# altimeter.net
KiCad netlist of a schematic drawn in EAGLE
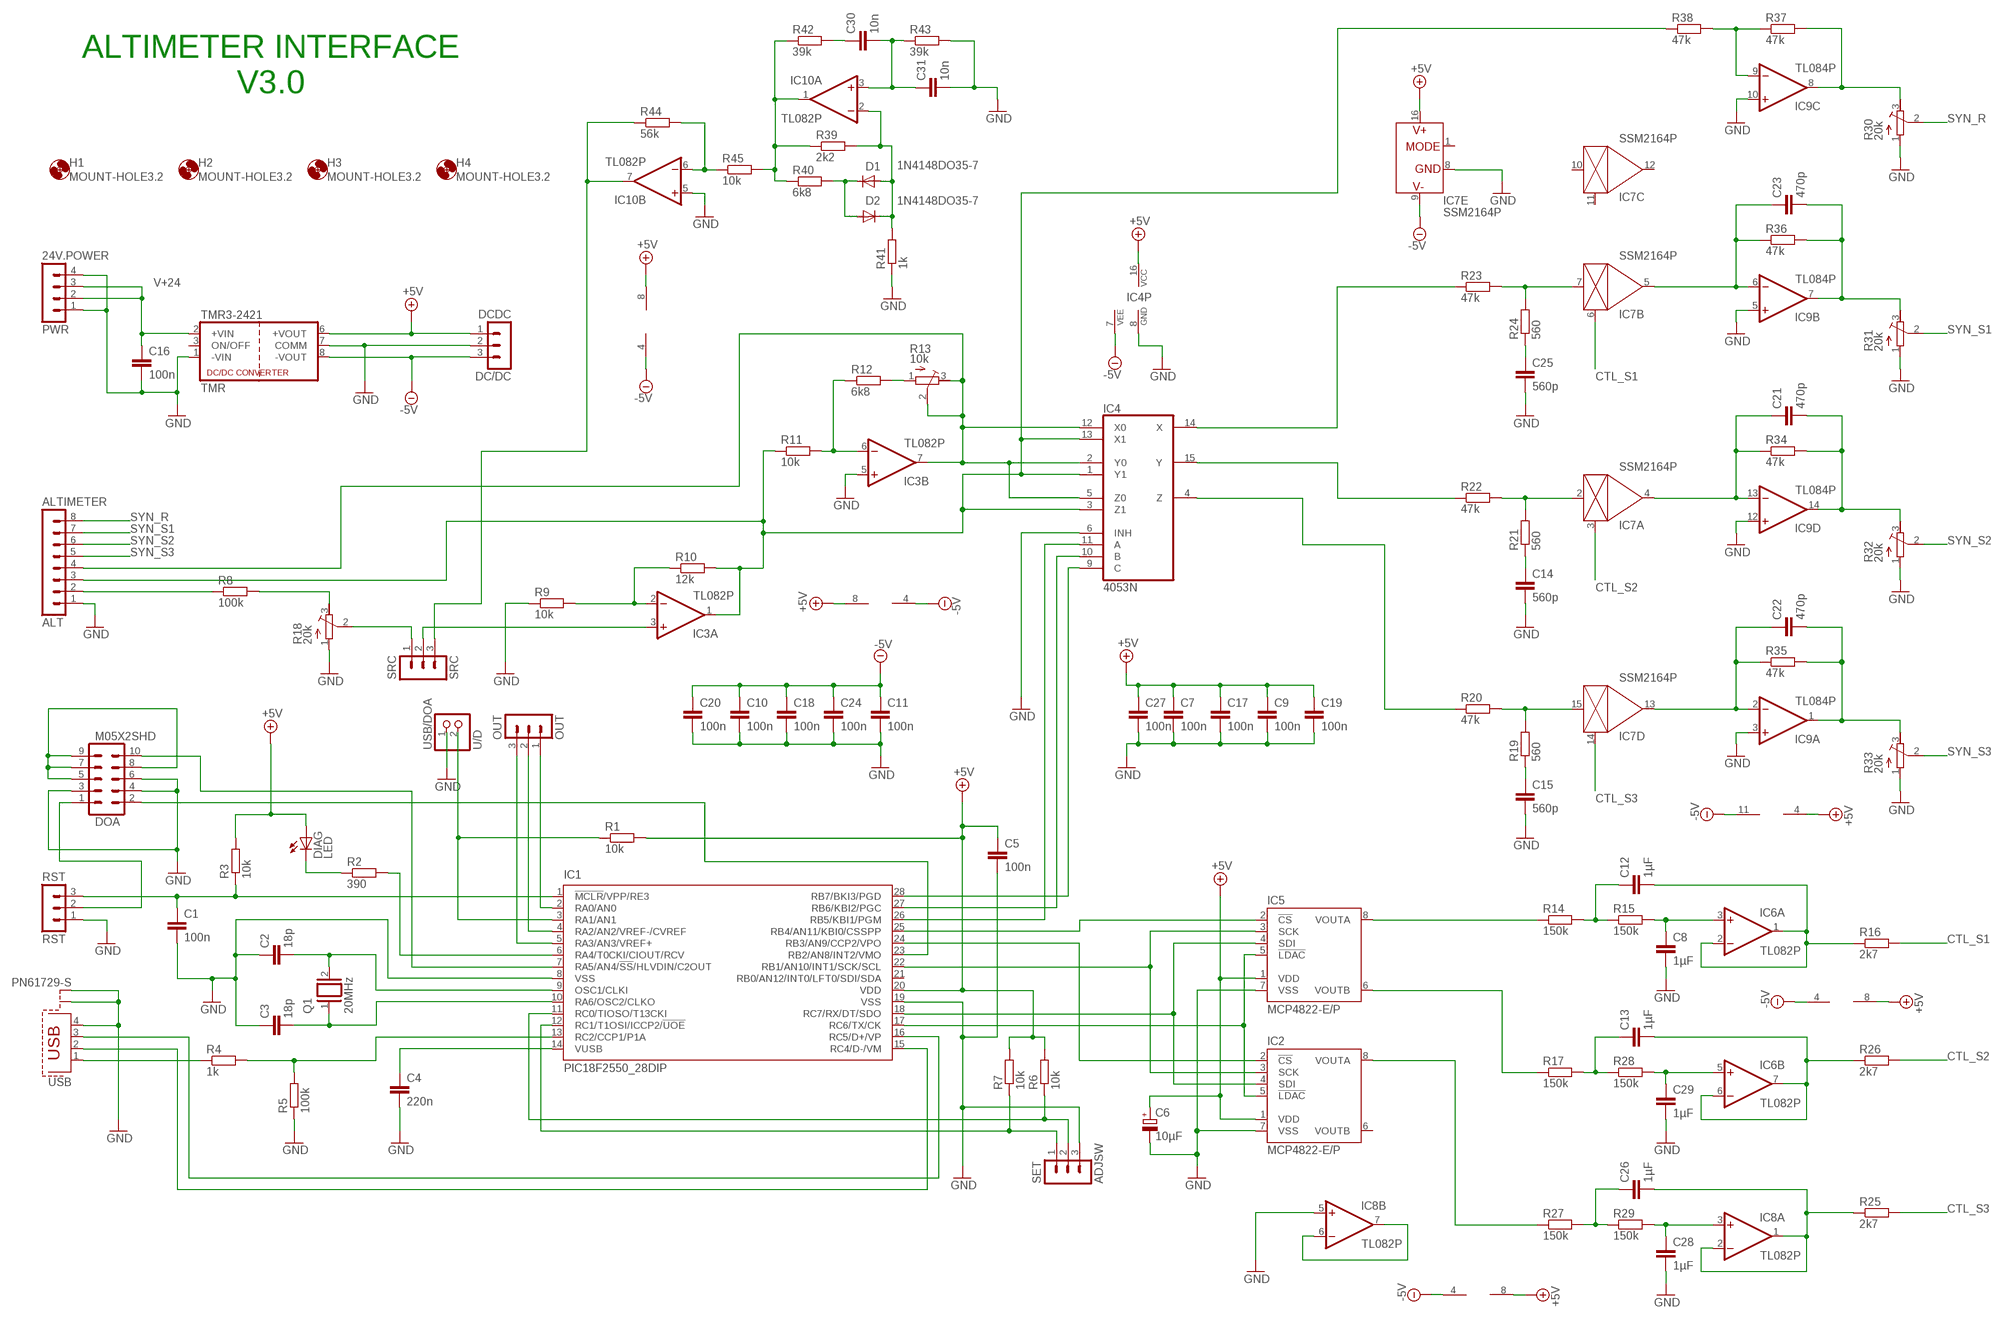
[diagram p0: schematic, sheet 1]

(export (version "E")
  (design (tool "Eeschema 10.0.6"))
  (components
    (comp (ref "24V.POWER")
      (value "PWR")
      (footprint "eagle-import:MA04-1")
      (libsource (lib "eagle-import") (part "MA04-1"))
    )
    (comp (ref "ADJSW")
      (value "SET")
      (footprint "eagle-import:MA03-1")
      (libsource (lib "eagle-import") (part "MA03-1"))
    )
    (comp (ref "ALTIMETER")
      (value "ALT")
      (footprint "eagle-import:MA08-1")
      (libsource (lib "eagle-import") (part "MA08-1"))
    )
    (comp (ref "C1")
      (value "100n")
      (footprint "eagle-import:C025-025X050")
      (libsource (lib "eagle-import") (part "C-EU025-025X050"))
    )
    (comp (ref "C2")
      (value "18p")
      (footprint "eagle-import:C025-025X050")
      (libsource (lib "eagle-import") (part "C-EU025-025X050"))
    )
    (comp (ref "C3")
      (value "18p")
      (footprint "eagle-import:C025-025X050")
      (libsource (lib "eagle-import") (part "C-EU025-025X050"))
    )
    (comp (ref "C4")
      (value "220n")
      (footprint "eagle-import:C5B3")
      (libsource (lib "eagle-import") (part "C5/3"))
    )
    (comp (ref "C5")
      (value "100n")
      (footprint "eagle-import:C025-025X050")
      (libsource (lib "eagle-import") (part "C-EU025-025X050"))
    )
    (comp (ref "C6")
      (value "10µF")
      (footprint "eagle-import:E2,5-5")
      (libsource (lib "eagle-import") (part "CPOL-EUE2.5-5"))
    )
    (comp (ref "C7")
      (value "100n")
      (footprint "eagle-import:C025-025X050")
      (libsource (lib "eagle-import") (part "C-EU025-025X050"))
    )
    (comp (ref "C8")
      (value "1µF")
      (footprint "eagle-import:C025-025X050")
      (libsource (lib "eagle-import") (part "C-EU025-025X050"))
    )
    (comp (ref "C9")
      (value "100n")
      (footprint "eagle-import:C025-025X050")
      (libsource (lib "eagle-import") (part "C-EU025-025X050"))
    )
    (comp (ref "C10")
      (value "100n")
      (footprint "eagle-import:C025-025X050")
      (libsource (lib "eagle-import") (part "C-EU025-025X050"))
    )
    (comp (ref "C11")
      (value "100n")
      (footprint "eagle-import:C025-025X050")
      (libsource (lib "eagle-import") (part "C-EU025-025X050"))
    )
    (comp (ref "C12")
      (value "1µF")
      (footprint "eagle-import:C025-025X050")
      (libsource (lib "eagle-import") (part "C-EU025-025X050"))
    )
    (comp (ref "C13")
      (value "1µF")
      (footprint "eagle-import:C025-025X050")
      (libsource (lib "eagle-import") (part "C-EU025-025X050"))
    )
    (comp (ref "C14")
      (value "560p")
      (footprint "eagle-import:C025-025X050")
      (libsource (lib "eagle-import") (part "C-EU025-025X050"))
    )
    (comp (ref "C15")
      (value "560p")
      (footprint "eagle-import:C025-025X050")
      (libsource (lib "eagle-import") (part "C-EU025-025X050"))
    )
    (comp (ref "C16")
      (value "100n")
      (footprint "eagle-import:C025-025X050")
      (libsource (lib "eagle-import") (part "C-EU025-025X050"))
    )
    (comp (ref "C17")
      (value "100n")
      (footprint "eagle-import:C025-025X050")
      (libsource (lib "eagle-import") (part "C-EU025-025X050"))
    )
    (comp (ref "C18")
      (value "100n")
      (footprint "eagle-import:C025-025X050")
      (libsource (lib "eagle-import") (part "C-EU025-025X050"))
    )
    (comp (ref "C19")
      (value "100n")
      (footprint "eagle-import:C025-025X050")
      (libsource (lib "eagle-import") (part "C-EU025-025X050"))
    )
    (comp (ref "C20")
      (value "100n")
      (footprint "eagle-import:C025-025X050")
      (libsource (lib "eagle-import") (part "C-EU025-025X050"))
    )
    (comp (ref "C21")
      (value "470p")
      (footprint "eagle-import:C025-025X050")
      (libsource (lib "eagle-import") (part "C-EU025-025X050"))
    )
    (comp (ref "C22")
      (value "470p")
      (footprint "eagle-import:C025-025X050")
      (libsource (lib "eagle-import") (part "C-EU025-025X050"))
    )
    (comp (ref "C23")
      (value "470p")
      (footprint "eagle-import:C025-025X050")
      (libsource (lib "eagle-import") (part "C-EU025-025X050"))
    )
    (comp (ref "C24")
      (value "100n")
      (footprint "eagle-import:C025-025X050")
      (libsource (lib "eagle-import") (part "C-EU025-025X050"))
    )
    (comp (ref "C25")
      (value "560p")
      (footprint "eagle-import:C025-025X050")
      (libsource (lib "eagle-import") (part "C-EU025-025X050"))
    )
    (comp (ref "C26")
      (value "1µF")
      (footprint "eagle-import:C025-025X050")
      (libsource (lib "eagle-import") (part "C-EU025-025X050"))
    )
    (comp (ref "C27")
      (value "100n")
      (footprint "eagle-import:C025-025X050")
      (libsource (lib "eagle-import") (part "C-EU025-025X050"))
    )
    (comp (ref "C28")
      (value "1µF")
      (footprint "eagle-import:C025-025X050")
      (libsource (lib "eagle-import") (part "C-EU025-025X050"))
    )
    (comp (ref "C29")
      (value "1µF")
      (footprint "eagle-import:C025-025X050")
      (libsource (lib "eagle-import") (part "C-EU025-025X050"))
    )
    (comp (ref "C30")
      (value "10n")
      (footprint "eagle-import:C025-025X050")
      (libsource (lib "eagle-import") (part "C-EU025-025X050"))
    )
    (comp (ref "C31")
      (value "10n")
      (footprint "eagle-import:C025-025X050")
      (libsource (lib "eagle-import") (part "C-EU025-025X050"))
    )
    (comp (ref "D1")
      (value "1N4148DO35-7")
      (footprint "eagle-import:DO35-7")
      (libsource (lib "eagle-import") (part "1N4148DO35-7"))
    )
    (comp (ref "D2")
      (value "1N4148DO35-7")
      (footprint "eagle-import:DO35-7")
      (libsource (lib "eagle-import") (part "1N4148DO35-7"))
    )
    (comp (ref "DC/DC")
      (value "DCDC")
      (footprint "eagle-import:MA03-1")
      (libsource (lib "eagle-import") (part "MA03-1"))
    )
    (comp (ref "DIAG")
      (value "LED")
      (footprint "eagle-import:LED3MM")
      (libsource (lib "eagle-import") (part "LED3MM"))
    )
    (comp (ref "DOA")
      (value "M05X2SHD")
      (footprint "eagle-import:2X5-SHROUDED")
      (libsource (lib "eagle-import") (part "M05X2SHD"))
    )
    (comp (ref "H1")
      (value "MOUNT-HOLE3.2")
      (footprint "eagle-import:3,2")
      (libsource (lib "eagle-import") (part "MOUNT-HOLE3.2"))
    )
    (comp (ref "H2")
      (value "MOUNT-HOLE3.2")
      (footprint "eagle-import:3,2")
      (libsource (lib "eagle-import") (part "MOUNT-HOLE3.2"))
    )
    (comp (ref "H3")
      (value "MOUNT-HOLE3.2")
      (footprint "eagle-import:3,2")
      (libsource (lib "eagle-import") (part "MOUNT-HOLE3.2"))
    )
    (comp (ref "H4")
      (value "MOUNT-HOLE3.2")
      (footprint "eagle-import:3,2")
      (libsource (lib "eagle-import") (part "MOUNT-HOLE3.2"))
    )
    (comp (ref "IC1")
      (value "PIC18F2550_28DIP")
      (footprint "eagle-import:DIL28-3")
      (fields (field (name "MF") "MICROCHIP") (field (name "MPN") "PIC18F2550-I/SP"))
      (libsource (lib "eagle-import") (part "PIC18F2_28DIP550"))
    )
    (comp (ref "IC2")
      (value "MCP4822-E/P")
      (footprint "eagle-import:DIL08")
      (libsource (lib "eagle-import") (part "MCP4822-E/P"))
    )
    (comp (ref "IC3")
      (value "TL082P")
      (footprint "eagle-import:DIL08")
      (libsource (lib "eagle-import") (part "TL082P"))
    )
    (comp (ref "IC4")
      (value "4053N")
      (footprint "eagle-import:DIL16")
      (libsource (lib "eagle-import") (part "4053N"))
    )
    (comp (ref "IC5")
      (value "MCP4822-E/P")
      (footprint "eagle-import:DIL08")
      (libsource (lib "eagle-import") (part "MCP4822-E/P"))
    )
    (comp (ref "IC6")
      (value "TL082P")
      (footprint "eagle-import:DIL08")
      (libsource (lib "eagle-import") (part "TL082P"))
    )
    (comp (ref "IC7")
      (value "SSM2164P")
      (footprint "eagle-import:DIL16")
      (libsource (lib "eagle-import") (part "SSM2164P"))
    )
    (comp (ref "IC8")
      (value "TL082P")
      (footprint "eagle-import:DIL08")
      (libsource (lib "eagle-import") (part "TL082P"))
    )
    (comp (ref "IC9")
      (value "TL084P")
      (footprint "eagle-import:DIL14")
      (libsource (lib "eagle-import") (part "TL084P"))
    )
    (comp (ref "IC10")
      (value "TL082P")
      (footprint "eagle-import:DIL08")
      (libsource (lib "eagle-import") (part "TL082P"))
    )
    (comp (ref "OUT")
      (value "OUT")
      (footprint "eagle-import:MA03-1")
      (libsource (lib "eagle-import") (part "MA03-1"))
    )
    (comp (ref "Q1")
      (value "20MHz")
      (footprint "eagle-import:QS")
      (libsource (lib "eagle-import") (part "XTAL/S"))
    )
    (comp (ref "R1")
      (value "10k")
      (footprint "eagle-import:0204_7")
      (libsource (lib "eagle-import") (part "R-EU_0204/7"))
    )
    (comp (ref "R2")
      (value "390")
      (footprint "eagle-import:0204_7")
      (libsource (lib "eagle-import") (part "R-EU_0204/7"))
    )
    (comp (ref "R3")
      (value "10k")
      (footprint "eagle-import:0204_7")
      (libsource (lib "eagle-import") (part "R-EU_0204/7"))
    )
    (comp (ref "R4")
      (value "1k")
      (footprint "eagle-import:0204_7")
      (libsource (lib "eagle-import") (part "R-EU_0204/7"))
    )
    (comp (ref "R5")
      (value "100k")
      (footprint "eagle-import:0204_7")
      (libsource (lib "eagle-import") (part "R-EU_0204/7"))
    )
    (comp (ref "R6")
      (value "10k")
      (footprint "eagle-import:0204_7")
      (libsource (lib "eagle-import") (part "R-EU_0204/7"))
    )
    (comp (ref "R7")
      (value "10k")
      (footprint "eagle-import:0204_7")
      (libsource (lib "eagle-import") (part "R-EU_0204/7"))
    )
    (comp (ref "R8")
      (value "100k")
      (footprint "eagle-import:0204_7")
      (libsource (lib "eagle-import") (part "R-EU_0204/7"))
    )
    (comp (ref "R9")
      (value "10k")
      (footprint "eagle-import:0204_7")
      (libsource (lib "eagle-import") (part "R-EU_0204/7"))
    )
    (comp (ref "R10")
      (value "12k")
      (footprint "eagle-import:0204_7")
      (libsource (lib "eagle-import") (part "R-EU_0204/7"))
    )
    (comp (ref "R11")
      (value "10k")
      (footprint "eagle-import:0204_7")
      (libsource (lib "eagle-import") (part "R-EU_0204/7"))
    )
    (comp (ref "R12")
      (value "6k8")
      (footprint "eagle-import:0204_7")
      (libsource (lib "eagle-import") (part "R-EU_0204/7"))
    )
    (comp (ref "R13")
      (value "10k")
      (footprint "eagle-import:RTRIM64Z")
      (libsource (lib "eagle-import") (part "R-TRIMM64Z"))
    )
    (comp (ref "R14")
      (value "150k")
      (footprint "eagle-import:0204_7")
      (libsource (lib "eagle-import") (part "R-EU_0204/7"))
    )
    (comp (ref "R15")
      (value "150k")
      (footprint "eagle-import:0204_7")
      (libsource (lib "eagle-import") (part "R-EU_0204/7"))
    )
    (comp (ref "R16")
      (value "2k7")
      (footprint "eagle-import:0204_7")
      (libsource (lib "eagle-import") (part "R-EU_0204/7"))
    )
    (comp (ref "R17")
      (value "150k")
      (footprint "eagle-import:0204_7")
      (libsource (lib "eagle-import") (part "R-EU_0204/7"))
    )
    (comp (ref "R18")
      (value "20k")
      (footprint "eagle-import:RTRIM64Z")
      (libsource (lib "eagle-import") (part "R-TRIMM64Z"))
    )
    (comp (ref "R19")
      (value "560")
      (footprint "eagle-import:0204_7")
      (libsource (lib "eagle-import") (part "R-EU_0204/7"))
    )
    (comp (ref "R20")
      (value "47k")
      (footprint "eagle-import:0204_7")
      (libsource (lib "eagle-import") (part "R-EU_0204/7"))
    )
    (comp (ref "R21")
      (value "560")
      (footprint "eagle-import:0204_7")
      (libsource (lib "eagle-import") (part "R-EU_0204/7"))
    )
    (comp (ref "R22")
      (value "47k")
      (footprint "eagle-import:0204_7")
      (libsource (lib "eagle-import") (part "R-EU_0204/7"))
    )
    (comp (ref "R23")
      (value "47k")
      (footprint "eagle-import:0204_7")
      (libsource (lib "eagle-import") (part "R-EU_0204/7"))
    )
    (comp (ref "R24")
      (value "560")
      (footprint "eagle-import:0204_7")
      (libsource (lib "eagle-import") (part "R-EU_0204/7"))
    )
    (comp (ref "R25")
      (value "2k7")
      (footprint "eagle-import:0204_7")
      (libsource (lib "eagle-import") (part "R-EU_0204/7"))
    )
    (comp (ref "R26")
      (value "2k7")
      (footprint "eagle-import:0204_7")
      (libsource (lib "eagle-import") (part "R-EU_0204/7"))
    )
    (comp (ref "R27")
      (value "150k")
      (footprint "eagle-import:0204_7")
      (libsource (lib "eagle-import") (part "R-EU_0204/7"))
    )
    (comp (ref "R28")
      (value "150k")
      (footprint "eagle-import:0204_7")
      (libsource (lib "eagle-import") (part "R-EU_0204/7"))
    )
    (comp (ref "R29")
      (value "150k")
      (footprint "eagle-import:0204_7")
      (libsource (lib "eagle-import") (part "R-EU_0204/7"))
    )
    (comp (ref "R30")
      (value "20k")
      (footprint "eagle-import:RTRIM64Z")
      (libsource (lib "eagle-import") (part "R-TRIMM64Z"))
    )
    (comp (ref "R31")
      (value "20k")
      (footprint "eagle-import:RTRIM64Z")
      (libsource (lib "eagle-import") (part "R-TRIMM64Z"))
    )
    (comp (ref "R32")
      (value "20k")
      (footprint "eagle-import:RTRIM64Z")
      (libsource (lib "eagle-import") (part "R-TRIMM64Z"))
    )
    (comp (ref "R33")
      (value "20k")
      (footprint "eagle-import:RTRIM64Z")
      (libsource (lib "eagle-import") (part "R-TRIMM64Z"))
    )
    (comp (ref "R34")
      (value "47k")
      (footprint "eagle-import:0204_7")
      (libsource (lib "eagle-import") (part "R-EU_0204/7"))
    )
    (comp (ref "R35")
      (value "47k")
      (footprint "eagle-import:0204_7")
      (libsource (lib "eagle-import") (part "R-EU_0204/7"))
    )
    (comp (ref "R36")
      (value "47k")
      (footprint "eagle-import:0204_7")
      (libsource (lib "eagle-import") (part "R-EU_0204/7"))
    )
    (comp (ref "R37")
      (value "47k")
      (footprint "eagle-import:0204_7")
      (libsource (lib "eagle-import") (part "R-EU_0204/7"))
    )
    (comp (ref "R38")
      (value "47k")
      (footprint "eagle-import:0204_7")
      (libsource (lib "eagle-import") (part "R-EU_0204/7"))
    )
    (comp (ref "R39")
      (value "2k2")
      (footprint "eagle-import:0204_7")
      (libsource (lib "eagle-import") (part "R-EU_0204/7"))
    )
    (comp (ref "R40")
      (value "6k8")
      (footprint "eagle-import:0204_7")
      (libsource (lib "eagle-import") (part "R-EU_0204/7"))
    )
    (comp (ref "R41")
      (value "1k")
      (footprint "eagle-import:0204_7")
      (libsource (lib "eagle-import") (part "R-EU_0204/7"))
    )
    (comp (ref "R42")
      (value "39k")
      (footprint "eagle-import:0204_7")
      (libsource (lib "eagle-import") (part "R-EU_0204/7"))
    )
    (comp (ref "R43")
      (value "39k")
      (footprint "eagle-import:0204_7")
      (libsource (lib "eagle-import") (part "R-EU_0204/7"))
    )
    (comp (ref "R44")
      (value "56k")
      (footprint "eagle-import:0204_7")
      (libsource (lib "eagle-import") (part "R-EU_0204/7"))
    )
    (comp (ref "R45")
      (value "10k")
      (footprint "eagle-import:0204_7")
      (libsource (lib "eagle-import") (part "R-EU_0204/7"))
    )
    (comp (ref "RST")
      (value "RST")
      (footprint "eagle-import:MA03-1")
      (libsource (lib "eagle-import") (part "MA03-1"))
    )
    (comp (ref "SRC")
      (value "SRC")
      (footprint "eagle-import:MA03-1")
      (libsource (lib "eagle-import") (part "MA03-1"))
    )
    (comp (ref "TMR3-2421")
      (value "TMR")
      (footprint "eagle-import:TRACO_SIP-8")
      (libsource (lib "eagle-import") (part "TMR"))
    )
    (comp (ref "USB")
      (value "PN61729-S")
      (footprint "eagle-import:PN61729-S")
      (libsource (lib "eagle-import") (part "PN61729-S"))
    )
    (comp (ref "USB/DOA")
      (value "U/D")
      (footprint "eagle-import:1X02")
      (libsource (lib "eagle-import") (part "PINHD-1X2"))
    )
  )
  (nets
    (net (code "1") (name "+5V") (class "Default")
      (node (ref "C17") (pin "1") (pinfunction "1_1") (pintype "passive"))
      (node (ref "C19") (pin "1") (pinfunction "1_1") (pintype "passive"))
      (node (ref "C27") (pin "1") (pinfunction "1_1") (pintype "passive"))
      (node (ref "C5") (pin "1") (pinfunction "1_1") (pintype "passive"))
      (node (ref "C6") (pin "+") (pinfunction "+_+") (pintype "passive"))
      (node (ref "C7") (pin "1") (pinfunction "1_1") (pintype "passive"))
      (node (ref "C9") (pin "1") (pinfunction "1_1") (pintype "passive"))
      (node (ref "DC/DC") (pin "1") (pinfunction "1_1") (pintype "passive"))
      (node (ref "DIAG") (pin "A") (pinfunction "A_A") (pintype "passive"))
      (node (ref "IC1") (pin "20") (pinfunction "VDD_20") (pintype "power_in"))
      (node (ref "IC10") (pin "8") (pinfunction "V+_8") (pintype "power_in"))
      (node (ref "IC2") (pin "1") (pinfunction "VDD_1") (pintype "power_in"))
      (node (ref "IC3") (pin "8") (pinfunction "V+_8") (pintype "power_in"))
      (node (ref "IC4") (pin "16") (pinfunction "VCC_16") (pintype "power_in"))
      (node (ref "IC5") (pin "1") (pinfunction "VDD_1") (pintype "power_in"))
      (node (ref "IC6") (pin "8") (pinfunction "V+_8") (pintype "power_in"))
      (node (ref "IC7") (pin "16") (pinfunction "V+_16") (pintype "power_in"))
      (node (ref "IC8") (pin "8") (pinfunction "V+_8") (pintype "power_in"))
      (node (ref "IC9") (pin "4") (pinfunction "V+_4") (pintype "power_in"))
      (node (ref "R1") (pin "2") (pinfunction "2_2") (pintype "passive"))
      (node (ref "R3") (pin "2") (pinfunction "2_2") (pintype "passive"))
      (node (ref "R6") (pin "2") (pinfunction "2_2") (pintype "passive"))
      (node (ref "R7") (pin "2") (pinfunction "2_2") (pintype "passive"))
      (node (ref "TMR3-2421") (pin "6") (pinfunction "+VOUT_6") (pintype "passive"))
    )
    (net (code "2") (name "-5V") (class "Default")
      (node (ref "C10") (pin "1") (pinfunction "1_1") (pintype "passive"))
      (node (ref "C11") (pin "1") (pinfunction "1_1") (pintype "passive"))
      (node (ref "C18") (pin "1") (pinfunction "1_1") (pintype "passive"))
      (node (ref "C20") (pin "1") (pinfunction "1_1") (pintype "passive"))
      (node (ref "C24") (pin "1") (pinfunction "1_1") (pintype "passive"))
      (node (ref "DC/DC") (pin "3") (pinfunction "3_3") (pintype "passive"))
      (node (ref "IC10") (pin "4") (pinfunction "V-_4") (pintype "power_in"))
      (node (ref "IC3") (pin "4") (pinfunction "V-_4") (pintype "power_in"))
      (node (ref "IC4") (pin "7") (pinfunction "VEE_7") (pintype "power_in"))
      (node (ref "IC6") (pin "4") (pinfunction "V-_4") (pintype "power_in"))
      (node (ref "IC7") (pin "9") (pinfunction "V-_9") (pintype "power_in"))
      (node (ref "IC8") (pin "4") (pinfunction "V-_4") (pintype "power_in"))
      (node (ref "IC9") (pin "11") (pinfunction "V-_11") (pintype "power_in"))
      (node (ref "TMR3-2421") (pin "8") (pinfunction "-VOUT_8") (pintype "passive"))
    )
    (net (code "3") (name "/CTL_S1") (class "Default")
      (node (ref "IC7") (pin "6") (pinfunction "CTRL_6") (pintype "input"))
      (node (ref "R16") (pin "2") (pinfunction "2_2") (pintype "passive"))
    )
    (net (code "4") (name "/CTL_S2") (class "Default")
      (node (ref "IC7") (pin "3") (pinfunction "CTRL_3") (pintype "input"))
      (node (ref "R26") (pin "2") (pinfunction "2_2") (pintype "passive"))
    )
    (net (code "5") (name "/CTL_S3") (class "Default")
      (node (ref "IC7") (pin "14") (pinfunction "CTRL_14") (pintype "input"))
      (node (ref "R25") (pin "2") (pinfunction "2_2") (pintype "passive"))
    )
    (net (code "6") (name "/SYN_R") (class "Default")
      (node (ref "ALTIMETER") (pin "8") (pinfunction "8_8") (pintype "passive"))
      (node (ref "R30") (pin "2") (pinfunction "S_2") (pintype "passive"))
    )
    (net (code "7") (name "/SYN_S1") (class "Default")
      (node (ref "ALTIMETER") (pin "7") (pinfunction "7_7") (pintype "passive"))
      (node (ref "R31") (pin "2") (pinfunction "S_2") (pintype "passive"))
    )
    (net (code "8") (name "/SYN_S2") (class "Default")
      (node (ref "ALTIMETER") (pin "6") (pinfunction "6_6") (pintype "passive"))
      (node (ref "R32") (pin "2") (pinfunction "S_2") (pintype "passive"))
    )
    (net (code "9") (name "/SYN_S3") (class "Default")
      (node (ref "ALTIMETER") (pin "5") (pinfunction "5_5") (pintype "passive"))
      (node (ref "R33") (pin "2") (pinfunction "S_2") (pintype "passive"))
    )
    (net (code "10") (name "/V+24") (class "Default")
      (node (ref "24V.POWER") (pin "2") (pinfunction "2_2") (pintype "passive"))
      (node (ref "24V.POWER") (pin "3") (pinfunction "3_3") (pintype "passive"))
      (node (ref "C16") (pin "1") (pinfunction "1_1") (pintype "passive"))
      (node (ref "TMR3-2421") (pin "2") (pinfunction "+VIN_2") (pintype "passive"))
    )
    (net (code "11") (name "GND") (class "Default")
      (node (ref "24V.POWER") (pin "1") (pinfunction "1_1") (pintype "passive"))
      (node (ref "24V.POWER") (pin "4") (pinfunction "4_4") (pintype "passive"))
      (node (ref "ADJSW") (pin "3") (pinfunction "3_3") (pintype "passive"))
      (node (ref "ALTIMETER") (pin "1") (pinfunction "1_1") (pintype "passive"))
      (node (ref "C1") (pin "2") (pinfunction "2_2") (pintype "passive"))
      (node (ref "C10") (pin "2") (pinfunction "2_2") (pintype "passive"))
      (node (ref "C11") (pin "2") (pinfunction "2_2") (pintype "passive"))
      (node (ref "C14") (pin "2") (pinfunction "2_2") (pintype "passive"))
      (node (ref "C15") (pin "2") (pinfunction "2_2") (pintype "passive"))
      (node (ref "C16") (pin "2") (pinfunction "2_2") (pintype "passive"))
      (node (ref "C17") (pin "2") (pinfunction "2_2") (pintype "passive"))
      (node (ref "C18") (pin "2") (pinfunction "2_2") (pintype "passive"))
      (node (ref "C19") (pin "2") (pinfunction "2_2") (pintype "passive"))
      (node (ref "C2") (pin "1") (pinfunction "1_1") (pintype "passive"))
      (node (ref "C20") (pin "2") (pinfunction "2_2") (pintype "passive"))
      (node (ref "C24") (pin "2") (pinfunction "2_2") (pintype "passive"))
      (node (ref "C25") (pin "2") (pinfunction "2_2") (pintype "passive"))
      (node (ref "C27") (pin "2") (pinfunction "2_2") (pintype "passive"))
      (node (ref "C28") (pin "2") (pinfunction "2_2") (pintype "passive"))
      (node (ref "C29") (pin "2") (pinfunction "2_2") (pintype "passive"))
      (node (ref "C3") (pin "1") (pinfunction "1_1") (pintype "passive"))
      (node (ref "C31") (pin "2") (pinfunction "2_2") (pintype "passive"))
      (node (ref "C4") (pin "2") (pinfunction "2_2") (pintype "passive"))
      (node (ref "C5") (pin "2") (pinfunction "2_2") (pintype "passive"))
      (node (ref "C6") (pin "-") (pinfunction "-_-") (pintype "passive"))
      (node (ref "C7") (pin "2") (pinfunction "2_2") (pintype "passive"))
      (node (ref "C8") (pin "2") (pinfunction "2_2") (pintype "passive"))
      (node (ref "C9") (pin "2") (pinfunction "2_2") (pintype "passive"))
      (node (ref "DC/DC") (pin "2") (pinfunction "2_2") (pintype "passive"))
      (node (ref "DOA") (pin "3") (pinfunction "3_3") (pintype "passive"))
      (node (ref "DOA") (pin "4") (pinfunction "4_4") (pintype "passive"))
      (node (ref "DOA") (pin "6") (pinfunction "6_6") (pintype "passive"))
      (node (ref "IC1") (pin "19") (pinfunction "VSS_19") (pintype "power_in"))
      (node (ref "IC1") (pin "8") (pinfunction "VSS_8") (pintype "power_in"))
      (node (ref "IC10") (pin "5") (pinfunction "+IN_5") (pintype "input"))
      (node (ref "IC2") (pin "7") (pinfunction "VSS_7") (pintype "power_in"))
      (node (ref "IC3") (pin "5") (pinfunction "+IN_5") (pintype "input"))
      (node (ref "IC4") (pin "6") (pinfunction "INH_6") (pintype "input"))
      (node (ref "IC4") (pin "8") (pinfunction "GND_8") (pintype "power_in"))
      (node (ref "IC5") (pin "7") (pinfunction "VSS_7") (pintype "power_in"))
      (node (ref "IC7") (pin "8") (pinfunction "GND_8") (pintype "power_in"))
      (node (ref "IC8") (pin "5") (pinfunction "+IN_5") (pintype "input"))
      (node (ref "IC9") (pin "10") (pinfunction "+IN_10") (pintype "input"))
      (node (ref "IC9") (pin "12") (pinfunction "+IN_12") (pintype "input"))
      (node (ref "IC9") (pin "3") (pinfunction "+IN_3") (pintype "input"))
      (node (ref "IC9") (pin "5") (pinfunction "+IN_5") (pintype "input"))
      (node (ref "R18") (pin "1") (pinfunction "A_1") (pintype "passive"))
      (node (ref "R30") (pin "1") (pinfunction "A_1") (pintype "passive"))
      (node (ref "R31") (pin "1") (pinfunction "A_1") (pintype "passive"))
      (node (ref "R32") (pin "1") (pinfunction "A_1") (pintype "passive"))
      (node (ref "R33") (pin "1") (pinfunction "A_1") (pintype "passive"))
      (node (ref "R41") (pin "1") (pinfunction "1_1") (pintype "passive"))
      (node (ref "R43") (pin "2") (pinfunction "2_2") (pintype "passive"))
      (node (ref "R5") (pin "1") (pinfunction "1_1") (pintype "passive"))
      (node (ref "R9") (pin "1") (pinfunction "1_1") (pintype "passive"))
      (node (ref "RST") (pin "1") (pinfunction "1_1") (pintype "passive"))
      (node (ref "TMR3-2421") (pin "1") (pinfunction "-VIN_1") (pintype "passive"))
      (node (ref "TMR3-2421") (pin "7") (pinfunction "COMM_7") (pintype "passive"))
      (node (ref "USB") (pin "4") (pinfunction "4_4") (pintype "passive"))
      (node (ref "USB") (pin "S1") (pinfunction "S1_S1") (pintype "passive"))
      (node (ref "USB") (pin "S2") (pinfunction "S2_S2") (pintype "passive"))
      (node (ref "USB/DOA") (pin "1") (pinfunction "1_1") (pintype "passive"))
    )
    (net (code "12") (name "Net-(ALTIMETER-Pad2)") (class "Default")
      (node (ref "ALTIMETER") (pin "2") (pinfunction "2_2") (pintype "passive"))
      (node (ref "R8") (pin "1") (pinfunction "1_1") (pintype "passive"))
    )
    (net (code "13") (name "Net-(C12-Pad1)") (class "Default")
      (node (ref "C12") (pin "1") (pinfunction "1_1") (pintype "passive"))
      (node (ref "R14") (pin "2") (pinfunction "2_2") (pintype "passive"))
      (node (ref "R15") (pin "1") (pinfunction "1_1") (pintype "passive"))
    )
    (net (code "14") (name "Net-(C13-Pad1)") (class "Default")
      (node (ref "C13") (pin "1") (pinfunction "1_1") (pintype "passive"))
      (node (ref "R17") (pin "2") (pinfunction "2_2") (pintype "passive"))
      (node (ref "R28") (pin "1") (pinfunction "1_1") (pintype "passive"))
    )
    (net (code "15") (name "Net-(C14-Pad1)") (class "Default")
      (node (ref "C14") (pin "1") (pinfunction "1_1") (pintype "passive"))
      (node (ref "R21") (pin "1") (pinfunction "1_1") (pintype "passive"))
    )
    (net (code "16") (name "Net-(C15-Pad1)") (class "Default")
      (node (ref "C15") (pin "1") (pinfunction "1_1") (pintype "passive"))
      (node (ref "R19") (pin "1") (pinfunction "1_1") (pintype "passive"))
    )
    (net (code "17") (name "Net-(C25-Pad1)") (class "Default")
      (node (ref "C25") (pin "1") (pinfunction "1_1") (pintype "passive"))
      (node (ref "R24") (pin "1") (pinfunction "1_1") (pintype "passive"))
    )
    (net (code "18") (name "Net-(C26-Pad1)") (class "Default")
      (node (ref "C26") (pin "1") (pinfunction "1_1") (pintype "passive"))
      (node (ref "R27") (pin "2") (pinfunction "2_2") (pintype "passive"))
      (node (ref "R29") (pin "1") (pinfunction "1_1") (pintype "passive"))
    )
    (net (code "19") (name "Net-(C30-Pad1)") (class "Default")
      (node (ref "C30") (pin "1") (pinfunction "1_1") (pintype "passive"))
      (node (ref "R42") (pin "2") (pinfunction "2_2") (pintype "passive"))
    )
    (net (code "20") (name "Net-(D1-PadC)") (class "Default")
      (node (ref "D1") (pin "C") (pinfunction "C_C") (pintype "passive"))
      (node (ref "D2") (pin "A") (pinfunction "A_A") (pintype "passive"))
      (node (ref "R40") (pin "2") (pinfunction "2_2") (pintype "passive"))
    )
    (net (code "21") (name "Net-(DIAG-C)") (class "Default")
      (node (ref "DIAG") (pin "K") (pinfunction "C_K") (pintype "passive"))
      (node (ref "R2") (pin "1") (pinfunction "1_1") (pintype "passive"))
    )
    (net (code "22") (name "Net-(DOA-Pad1)") (class "Default")
      (node (ref "DOA") (pin "1") (pinfunction "1_1") (pintype "passive"))
      (node (ref "RST") (pin "2") (pinfunction "2_2") (pintype "passive"))
    )
    (net (code "23") (name "Net-(DOA-Pad5)") (class "Default")
      (node (ref "DOA") (pin "5") (pinfunction "5_5") (pintype "passive"))
      (node (ref "DOA") (pin "7") (pinfunction "7_7") (pintype "passive"))
      (node (ref "DOA") (pin "8") (pinfunction "8_8") (pintype "passive"))
      (node (ref "DOA") (pin "9") (pinfunction "9_9") (pintype "passive"))
    )
    (net (code "24") (name "Net-(IC1-OSC1{slash}CLKI)") (class "Default")
      (node (ref "C2") (pin "2") (pinfunction "2_2") (pintype "passive"))
      (node (ref "IC1") (pin "9") (pinfunction "OSC1/CLKI_9") (pintype "input"))
      (node (ref "Q1") (pin "2") (pinfunction "2_2") (pintype "passive"))
    )
    (net (code "25") (name "Net-(IC1-RA0{slash}AN0)") (class "Default")
      (node (ref "IC1") (pin "2") (pinfunction "RA0/AN0_2") (pintype "bidirectional"))
      (node (ref "OUT") (pin "1") (pinfunction "1_1") (pintype "passive"))
    )
    (net (code "26") (name "Net-(IC1-RA1{slash}AN1)") (class "Default")
      (node (ref "IC1") (pin "3") (pinfunction "RA1/AN1_3") (pintype "bidirectional"))
      (node (ref "R1") (pin "1") (pinfunction "1_1") (pintype "passive"))
      (node (ref "USB/DOA") (pin "2") (pinfunction "2_2") (pintype "passive"))
    )
    (net (code "27") (name "Net-(IC1-RA2{slash}AN2{slash}VREF-{slash}CVREF)") (class "Default")
      (node (ref "IC1") (pin "4") (pinfunction "RA2/AN2/VREF-/CVREF_4") (pintype "bidirectional"))
      (node (ref "OUT") (pin "2") (pinfunction "2_2") (pintype "passive"))
    )
    (net (code "28") (name "Net-(IC1-RA3{slash}AN3{slash}VREF+)") (class "Default")
      (node (ref "IC1") (pin "5") (pinfunction "RA3/AN3/VREF+_5") (pintype "bidirectional"))
      (node (ref "OUT") (pin "3") (pinfunction "3_3") (pintype "passive"))
    )
    (net (code "29") (name "Net-(IC1-RA4{slash}T0CKI{slash}CIOUT{slash}RCV)") (class "Default")
      (node (ref "IC1") (pin "6") (pinfunction "RA4/T0CKI/CIOUT/RCV_6") (pintype "bidirectional"))
      (node (ref "R2") (pin "2") (pinfunction "2_2") (pintype "passive"))
    )
    (net (code "30") (name "Net-(IC1-RA5{slash}AN4{slash}~{SS}{slash}HLVDIN{slash}C2OUT)") (class "Default")
      (node (ref "DOA") (pin "10") (pinfunction "10_10") (pintype "passive"))
      (node (ref "IC1") (pin "7") (pinfunction "RA5/AN4/~{SS}/HLVDIN/C2OUT_7") (pintype "bidirectional"))
    )
    (net (code "31") (name "Net-(IC1-RA6{slash}OSC2{slash}CLKO)") (class "Default")
      (node (ref "C3") (pin "2") (pinfunction "2_2") (pintype "passive"))
      (node (ref "IC1") (pin "10") (pinfunction "RA6/OSC2/CLKO_10") (pintype "output"))
      (node (ref "Q1") (pin "1") (pinfunction "1_1") (pintype "passive"))
    )
    (net (code "32") (name "Net-(IC1-RB1{slash}AN10{slash}INT1{slash}SCK{slash}SCL)") (class "Default")
      (node (ref "IC1") (pin "22") (pinfunction "RB1/AN10/INT1/SCK/SCL_22") (pintype "bidirectional"))
      (node (ref "IC2") (pin "3") (pinfunction "SCK_3") (pintype "input"))
      (node (ref "IC5") (pin "3") (pinfunction "SCK_3") (pintype "input"))
    )
    (net (code "33") (name "Net-(IC1-RB2{slash}AN8{slash}INT2{slash}VMO)") (class "Default")
      (node (ref "DOA") (pin "2") (pinfunction "2_2") (pintype "passive"))
      (node (ref "IC1") (pin "23") (pinfunction "RB2/AN8/INT2/VMO_23") (pintype "bidirectional"))
    )
    (net (code "34") (name "Net-(IC1-RB3{slash}AN9{slash}CCP2{slash}VPO)") (class "Default")
      (node (ref "IC1") (pin "24") (pinfunction "RB3/AN9/CCP2/VPO_24") (pintype "bidirectional"))
      (node (ref "IC2") (pin "2") (pinfunction "~{CS}_2") (pintype "input"))
    )
    (net (code "35") (name "Net-(IC1-RB4{slash}AN11{slash}KBI0{slash}CSSPP)") (class "Default")
      (node (ref "IC1") (pin "25") (pinfunction "RB4/AN11/KBI0/CSSPP_25") (pintype "bidirectional"))
      (node (ref "IC5") (pin "2") (pinfunction "~{CS}_2") (pintype "input"))
    )
    (net (code "36") (name "Net-(IC1-RB5{slash}KBI1{slash}PGM)") (class "Default")
      (node (ref "IC1") (pin "26") (pinfunction "RB5/KBI1/PGM_26") (pintype "bidirectional"))
      (node (ref "IC4") (pin "11") (pinfunction "A_11") (pintype "input"))
    )
    (net (code "37") (name "Net-(IC1-RB6{slash}KBI2{slash}PGC)") (class "Default")
      (node (ref "IC1") (pin "27") (pinfunction "RB6/KBI2/PGC_27") (pintype "bidirectional"))
      (node (ref "IC4") (pin "10") (pinfunction "B_10") (pintype "input"))
    )
    (net (code "38") (name "Net-(IC1-RB7{slash}BKI3{slash}PGD)") (class "Default")
      (node (ref "IC1") (pin "28") (pinfunction "RB7/BKI3/PGD_28") (pintype "bidirectional"))
      (node (ref "IC4") (pin "9") (pinfunction "C_9") (pintype "input"))
    )
    (net (code "39") (name "Net-(IC1-RC0{slash}TIOSO{slash}T13CKI)") (class "Default")
      (node (ref "ADJSW") (pin "2") (pinfunction "2_2") (pintype "passive"))
      (node (ref "IC1") (pin "11") (pinfunction "RC0/TIOSO/T13CKI_11") (pintype "bidirectional"))
      (node (ref "R6") (pin "1") (pinfunction "1_1") (pintype "passive"))
    )
    (net (code "40") (name "Net-(IC1-RC1{slash}T1OSI{slash}ICCP2{slash}~{UOE})") (class "Default")
      (node (ref "ADJSW") (pin "1") (pinfunction "1_1") (pintype "passive"))
      (node (ref "IC1") (pin "12") (pinfunction "RC1/T1OSI/ICCP2/~{UOE}_12") (pintype "bidirectional"))
      (node (ref "R7") (pin "1") (pinfunction "1_1") (pintype "passive"))
    )
    (net (code "41") (name "Net-(IC1-RC2{slash}CCP1{slash}P1A)") (class "Default")
      (node (ref "IC1") (pin "13") (pinfunction "RC2/CCP1/P1A_13") (pintype "bidirectional"))
      (node (ref "R4") (pin "2") (pinfunction "2_2") (pintype "passive"))
      (node (ref "R5") (pin "2") (pinfunction "2_2") (pintype "passive"))
    )
    (net (code "42") (name "Net-(IC1-RC4{slash}D-{slash}VM)") (class "Default")
      (node (ref "IC1") (pin "15") (pinfunction "RC4/D-/VM_15") (pintype "bidirectional"))
      (node (ref "USB") (pin "2") (pinfunction "2_2") (pintype "passive"))
    )
    (net (code "43") (name "Net-(IC1-RC5{slash}D+{slash}VP)") (class "Default")
      (node (ref "IC1") (pin "16") (pinfunction "RC5/D+/VP_16") (pintype "bidirectional"))
      (node (ref "USB") (pin "3") (pinfunction "3_3") (pintype "passive"))
    )
    (net (code "44") (name "Net-(IC1-RC6{slash}TX{slash}CK)") (class "Default")
      (node (ref "IC1") (pin "17") (pinfunction "RC6/TX/CK_17") (pintype "bidirectional"))
      (node (ref "IC2") (pin "5") (pinfunction "~{LDAC}_5") (pintype "input"))
      (node (ref "IC5") (pin "5") (pinfunction "~{LDAC}_5") (pintype "input"))
    )
    (net (code "45") (name "Net-(IC1-RC7{slash}RX{slash}DT{slash}SDO)") (class "Default")
      (node (ref "IC1") (pin "18") (pinfunction "RC7/RX/DT/SDO_18") (pintype "bidirectional"))
      (node (ref "IC2") (pin "4") (pinfunction "SDI_4") (pintype "input"))
      (node (ref "IC5") (pin "4") (pinfunction "SDI_4") (pintype "input"))
    )
    (net (code "46") (name "Net-(IC1-VUSB)") (class "Default")
      (node (ref "C4") (pin "1") (pinfunction "1_1") (pintype "passive"))
      (node (ref "IC1") (pin "14") (pinfunction "VUSB_14") (pintype "bidirectional"))
    )
    (net (code "47") (name "Net-(IC1-~{MCLR}{slash}VPP{slash}RE3)") (class "Default")
      (node (ref "C1") (pin "1") (pinfunction "1_1") (pintype "passive"))
      (node (ref "IC1") (pin "1") (pinfunction "~{MCLR}/VPP/RE3_1") (pintype "input"))
      (node (ref "R3") (pin "1") (pinfunction "1_1") (pintype "passive"))
      (node (ref "RST") (pin "3") (pinfunction "3_3") (pintype "passive"))
    )
    (net (code "48") (name "Net-(IC2-VOUTA)") (class "Default")
      (node (ref "IC2") (pin "8") (pinfunction "VOUTA_8") (pintype "output"))
      (node (ref "R27") (pin "1") (pinfunction "1_1") (pintype "passive"))
    )
    (net (code "49") (name "Net-(IC3A-+IN)") (class "Default")
      (node (ref "IC3") (pin "3") (pinfunction "+IN_3") (pintype "input"))
      (node (ref "SRC") (pin "2") (pinfunction "2_2") (pintype "passive"))
    )
    (net (code "50") (name "Net-(IC3A--IN)") (class "Default")
      (node (ref "IC3") (pin "2") (pinfunction "-IN_2") (pintype "input"))
      (node (ref "R10") (pin "1") (pinfunction "1_1") (pintype "passive"))
      (node (ref "R9") (pin "2") (pinfunction "2_2") (pintype "passive"))
    )
    (net (code "51") (name "Net-(IC3A-OUT)") (class "Default")
      (node (ref "ALTIMETER") (pin "3") (pinfunction "3_3") (pintype "passive"))
      (node (ref "IC3") (pin "1") (pinfunction "OUT_1") (pintype "output"))
      (node (ref "IC4") (pin "1") (pinfunction "Y1_1") (pintype "bidirectional"))
      (node (ref "IC4") (pin "13") (pinfunction "X1_13") (pintype "bidirectional"))
      (node (ref "IC4") (pin "3") (pinfunction "Z1_3") (pintype "bidirectional"))
      (node (ref "R10") (pin "2") (pinfunction "2_2") (pintype "passive"))
      (node (ref "R11") (pin "1") (pinfunction "1_1") (pintype "passive"))
      (node (ref "R38") (pin "1") (pinfunction "1_1") (pintype "passive"))
    )
    (net (code "52") (name "Net-(IC3B--IN)") (class "Default")
      (node (ref "IC3") (pin "6") (pinfunction "-IN_6") (pintype "input"))
      (node (ref "R11") (pin "2") (pinfunction "2_2") (pintype "passive"))
      (node (ref "R12") (pin "1") (pinfunction "1_1") (pintype "passive"))
    )
    (net (code "53") (name "Net-(IC3B-OUT)") (class "Default")
      (node (ref "ALTIMETER") (pin "4") (pinfunction "4_4") (pintype "passive"))
      (node (ref "IC3") (pin "7") (pinfunction "OUT_7") (pintype "output"))
      (node (ref "IC4") (pin "12") (pinfunction "X0_12") (pintype "bidirectional"))
      (node (ref "IC4") (pin "2") (pinfunction "Y0_2") (pintype "bidirectional"))
      (node (ref "IC4") (pin "5") (pinfunction "Z0_5") (pintype "bidirectional"))
      (node (ref "R13") (pin "2") (pinfunction "S_2") (pintype "passive"))
      (node (ref "R13") (pin "3") (pinfunction "E_3") (pintype "passive"))
    )
    (net (code "54") (name "Net-(IC4A-X)") (class "Default")
      (node (ref "IC4") (pin "14") (pinfunction "X_14") (pintype "bidirectional"))
      (node (ref "R23") (pin "1") (pinfunction "1_1") (pintype "passive"))
    )
    (net (code "55") (name "Net-(IC4A-Y)") (class "Default")
      (node (ref "IC4") (pin "15") (pinfunction "Y_15") (pintype "bidirectional"))
      (node (ref "R22") (pin "1") (pinfunction "1_1") (pintype "passive"))
    )
    (net (code "56") (name "Net-(IC4A-Z)") (class "Default")
      (node (ref "IC4") (pin "4") (pinfunction "Z_4") (pintype "bidirectional"))
      (node (ref "R20") (pin "1") (pinfunction "1_1") (pintype "passive"))
    )
    (net (code "57") (name "Net-(IC5-VOUTA)") (class "Default")
      (node (ref "IC5") (pin "8") (pinfunction "VOUTA_8") (pintype "output"))
      (node (ref "R14") (pin "1") (pinfunction "1_1") (pintype "passive"))
    )
    (net (code "58") (name "Net-(IC5-VOUTB)") (class "Default")
      (node (ref "IC5") (pin "6") (pinfunction "VOUTB_6") (pintype "output"))
      (node (ref "R17") (pin "1") (pinfunction "1_1") (pintype "passive"))
    )
    (net (code "59") (name "Net-(IC6A-+IN)") (class "Default")
      (node (ref "C8") (pin "1") (pinfunction "1_1") (pintype "passive"))
      (node (ref "IC6") (pin "3") (pinfunction "+IN_3") (pintype "input"))
      (node (ref "R15") (pin "2") (pinfunction "2_2") (pintype "passive"))
    )
    (net (code "60") (name "Net-(IC6A--IN)") (class "Default")
      (node (ref "C12") (pin "2") (pinfunction "2_2") (pintype "passive"))
      (node (ref "IC6") (pin "1") (pinfunction "OUT_1") (pintype "output"))
      (node (ref "IC6") (pin "2") (pinfunction "-IN_2") (pintype "input"))
      (node (ref "R16") (pin "1") (pinfunction "1_1") (pintype "passive"))
    )
    (net (code "61") (name "Net-(IC6B-+IN)") (class "Default")
      (node (ref "C29") (pin "1") (pinfunction "1_1") (pintype "passive"))
      (node (ref "IC6") (pin "5") (pinfunction "+IN_5") (pintype "input"))
      (node (ref "R28") (pin "2") (pinfunction "2_2") (pintype "passive"))
    )
    (net (code "62") (name "Net-(IC6B--IN)") (class "Default")
      (node (ref "C13") (pin "2") (pinfunction "2_2") (pintype "passive"))
      (node (ref "IC6") (pin "6") (pinfunction "-IN_6") (pintype "input"))
      (node (ref "IC6") (pin "7") (pinfunction "OUT_7") (pintype "output"))
      (node (ref "R26") (pin "1") (pinfunction "1_1") (pintype "passive"))
    )
    (net (code "63") (name "Net-(IC7A-IN)") (class "Default")
      (node (ref "IC7") (pin "2") (pinfunction "IN_2") (pintype "input"))
      (node (ref "R21") (pin "2") (pinfunction "2_2") (pintype "passive"))
      (node (ref "R22") (pin "2") (pinfunction "2_2") (pintype "passive"))
    )
    (net (code "64") (name "Net-(IC7A-OUT)") (class "Default")
      (node (ref "C21") (pin "1") (pinfunction "1_1") (pintype "passive"))
      (node (ref "IC7") (pin "4") (pinfunction "OUT_4") (pintype "output"))
      (node (ref "IC9") (pin "13") (pinfunction "-IN_13") (pintype "input"))
      (node (ref "R34") (pin "1") (pinfunction "1_1") (pintype "passive"))
    )
    (net (code "65") (name "Net-(IC7B-IN)") (class "Default")
      (node (ref "IC7") (pin "7") (pinfunction "IN_7") (pintype "input"))
      (node (ref "R23") (pin "2") (pinfunction "2_2") (pintype "passive"))
      (node (ref "R24") (pin "2") (pinfunction "2_2") (pintype "passive"))
    )
    (net (code "66") (name "Net-(IC7B-OUT)") (class "Default")
      (node (ref "C23") (pin "1") (pinfunction "1_1") (pintype "passive"))
      (node (ref "IC7") (pin "5") (pinfunction "OUT_5") (pintype "output"))
      (node (ref "IC9") (pin "6") (pinfunction "-IN_6") (pintype "input"))
      (node (ref "R36") (pin "1") (pinfunction "1_1") (pintype "passive"))
    )
    (net (code "67") (name "Net-(IC7D-IN)") (class "Default")
      (node (ref "IC7") (pin "15") (pinfunction "IN_15") (pintype "input"))
      (node (ref "R19") (pin "2") (pinfunction "2_2") (pintype "passive"))
      (node (ref "R20") (pin "2") (pinfunction "2_2") (pintype "passive"))
    )
    (net (code "68") (name "Net-(IC7D-OUT)") (class "Default")
      (node (ref "C22") (pin "1") (pinfunction "1_1") (pintype "passive"))
      (node (ref "IC7") (pin "13") (pinfunction "OUT_13") (pintype "output"))
      (node (ref "IC9") (pin "2") (pinfunction "-IN_2") (pintype "input"))
      (node (ref "R35") (pin "1") (pinfunction "1_1") (pintype "passive"))
    )
    (net (code "69") (name "Net-(IC8A-+IN)") (class "Default")
      (node (ref "C28") (pin "1") (pinfunction "1_1") (pintype "passive"))
      (node (ref "IC8") (pin "3") (pinfunction "+IN_3") (pintype "input"))
      (node (ref "R29") (pin "2") (pinfunction "2_2") (pintype "passive"))
    )
    (net (code "70") (name "Net-(IC8A--IN)") (class "Default")
      (node (ref "C26") (pin "2") (pinfunction "2_2") (pintype "passive"))
      (node (ref "IC8") (pin "1") (pinfunction "OUT_1") (pintype "output"))
      (node (ref "IC8") (pin "2") (pinfunction "-IN_2") (pintype "input"))
      (node (ref "R25") (pin "1") (pinfunction "1_1") (pintype "passive"))
    )
    (net (code "71") (name "Net-(IC8B--IN)") (class "Default")
      (node (ref "IC8") (pin "6") (pinfunction "-IN_6") (pintype "input"))
      (node (ref "IC8") (pin "7") (pinfunction "OUT_7") (pintype "output"))
    )
    (net (code "72") (name "Net-(IC9A-OUT)") (class "Default")
      (node (ref "C22") (pin "2") (pinfunction "2_2") (pintype "passive"))
      (node (ref "IC9") (pin "1") (pinfunction "OUT_1") (pintype "output"))
      (node (ref "R33") (pin "3") (pinfunction "E_3") (pintype "passive"))
      (node (ref "R35") (pin "2") (pinfunction "2_2") (pintype "passive"))
    )
    (net (code "73") (name "Net-(IC9B-OUT)") (class "Default")
      (node (ref "C23") (pin "2") (pinfunction "2_2") (pintype "passive"))
      (node (ref "IC9") (pin "7") (pinfunction "OUT_7") (pintype "output"))
      (node (ref "R31") (pin "3") (pinfunction "E_3") (pintype "passive"))
      (node (ref "R36") (pin "2") (pinfunction "2_2") (pintype "passive"))
    )
    (net (code "74") (name "Net-(IC9C--IN)") (class "Default")
      (node (ref "IC9") (pin "9") (pinfunction "-IN_9") (pintype "input"))
      (node (ref "R37") (pin "1") (pinfunction "1_1") (pintype "passive"))
      (node (ref "R38") (pin "2") (pinfunction "2_2") (pintype "passive"))
    )
    (net (code "75") (name "Net-(IC9C-OUT)") (class "Default")
      (node (ref "IC9") (pin "8") (pinfunction "OUT_8") (pintype "output"))
      (node (ref "R30") (pin "3") (pinfunction "E_3") (pintype "passive"))
      (node (ref "R37") (pin "2") (pinfunction "2_2") (pintype "passive"))
    )
    (net (code "76") (name "Net-(IC9D-OUT)") (class "Default")
      (node (ref "C21") (pin "2") (pinfunction "2_2") (pintype "passive"))
      (node (ref "IC9") (pin "14") (pinfunction "OUT_14") (pintype "output"))
      (node (ref "R32") (pin "3") (pinfunction "E_3") (pintype "passive"))
      (node (ref "R34") (pin "2") (pinfunction "2_2") (pintype "passive"))
    )
    (net (code "77") (name "Net-(IC10A-+IN)") (class "Default")
      (node (ref "C30") (pin "2") (pinfunction "2_2") (pintype "passive"))
      (node (ref "C31") (pin "1") (pinfunction "1_1") (pintype "passive"))
      (node (ref "IC10") (pin "3") (pinfunction "+IN_3") (pintype "input"))
      (node (ref "R43") (pin "1") (pinfunction "1_1") (pintype "passive"))
    )
    (net (code "78") (name "Net-(IC10A--IN)") (class "Default")
      (node (ref "D1") (pin "A") (pinfunction "A_A") (pintype "passive"))
      (node (ref "D2") (pin "C") (pinfunction "C_C") (pintype "passive"))
      (node (ref "IC10") (pin "2") (pinfunction "-IN_2") (pintype "input"))
      (node (ref "R39") (pin "2") (pinfunction "2_2") (pintype "passive"))
      (node (ref "R41") (pin "2") (pinfunction "2_2") (pintype "passive"))
    )
    (net (code "79") (name "Net-(IC10A-OUT)") (class "Default")
      (node (ref "IC10") (pin "1") (pinfunction "OUT_1") (pintype "output"))
      (node (ref "R39") (pin "1") (pinfunction "1_1") (pintype "passive"))
      (node (ref "R40") (pin "1") (pinfunction "1_1") (pintype "passive"))
      (node (ref "R42") (pin "1") (pinfunction "1_1") (pintype "passive"))
      (node (ref "R45") (pin "2") (pinfunction "2_2") (pintype "passive"))
    )
    (net (code "80") (name "Net-(IC10B--IN)") (class "Default")
      (node (ref "IC10") (pin "6") (pinfunction "-IN_6") (pintype "input"))
      (node (ref "R44") (pin "2") (pinfunction "2_2") (pintype "passive"))
      (node (ref "R45") (pin "1") (pinfunction "1_1") (pintype "passive"))
    )
    (net (code "81") (name "Net-(IC10B-OUT)") (class "Default")
      (node (ref "IC10") (pin "7") (pinfunction "OUT_7") (pintype "output"))
      (node (ref "R44") (pin "1") (pinfunction "1_1") (pintype "passive"))
      (node (ref "SRC") (pin "3") (pinfunction "3_3") (pintype "passive"))
    )
    (net (code "82") (name "Net-(R4-Pad1)") (class "Default")
      (node (ref "R4") (pin "1") (pinfunction "1_1") (pintype "passive"))
      (node (ref "USB") (pin "1") (pinfunction "1_1") (pintype "passive"))
    )
    (net (code "83") (name "Net-(R13-A)") (class "Default")
      (node (ref "R12") (pin "2") (pinfunction "2_2") (pintype "passive"))
      (node (ref "R13") (pin "1") (pinfunction "A_1") (pintype "passive"))
    )
    (net (code "84") (name "Net-(R18-E)") (class "Default")
      (node (ref "R18") (pin "3") (pinfunction "E_3") (pintype "passive"))
      (node (ref "R8") (pin "2") (pinfunction "2_2") (pintype "passive"))
    )
    (net (code "85") (name "Net-(R18-S)") (class "Default")
      (node (ref "R18") (pin "2") (pinfunction "S_2") (pintype "passive"))
      (node (ref "SRC") (pin "1") (pinfunction "1_1") (pintype "passive"))
    )
    (net (code "86") (name "unconnected-(IC1-RB0{slash}AN12{slash}INT0{slash}LFT0{slash}SDI{slash}SDA-Pad21)") (class "Default")
      (node (ref "IC1") (pin "21") (pinfunction "RB0/AN12/INT0/LFT0/SDI/SDA_21") (pintype "bidirectional"))
    )
    (net (code "87") (name "unconnected-(IC2-VOUTB-Pad6)") (class "Default")
      (node (ref "IC2") (pin "6") (pinfunction "VOUTB_6") (pintype "output"))
    )
    (net (code "88") (name "unconnected-(IC7C-CTRL-Pad11)") (class "Default")
      (node (ref "IC7") (pin "11") (pinfunction "CTRL_11") (pintype "input"))
    )
    (net (code "89") (name "unconnected-(IC7C-IN-Pad10)") (class "Default")
      (node (ref "IC7") (pin "10") (pinfunction "IN_10") (pintype "input"))
    )
    (net (code "90") (name "unconnected-(IC7C-OUT-Pad12)") (class "Default")
      (node (ref "IC7") (pin "12") (pinfunction "OUT_12") (pintype "output"))
    )
    (net (code "91") (name "unconnected-(IC7E-MODE-Pad1)") (class "Default")
      (node (ref "IC7") (pin "1") (pinfunction "MODE_1") (pintype "input"))
    )
    (net (code "92") (name "unconnected-(TMR3-2421-ON{slash}OFF-Pad3)") (class "Default")
      (node (ref "TMR3-2421") (pin "3") (pinfunction "ON/OFF_3") (pintype "passive"))
    )
  )
)
